# meped.net
KiCad netlist of a schematic drawn in EAGLE
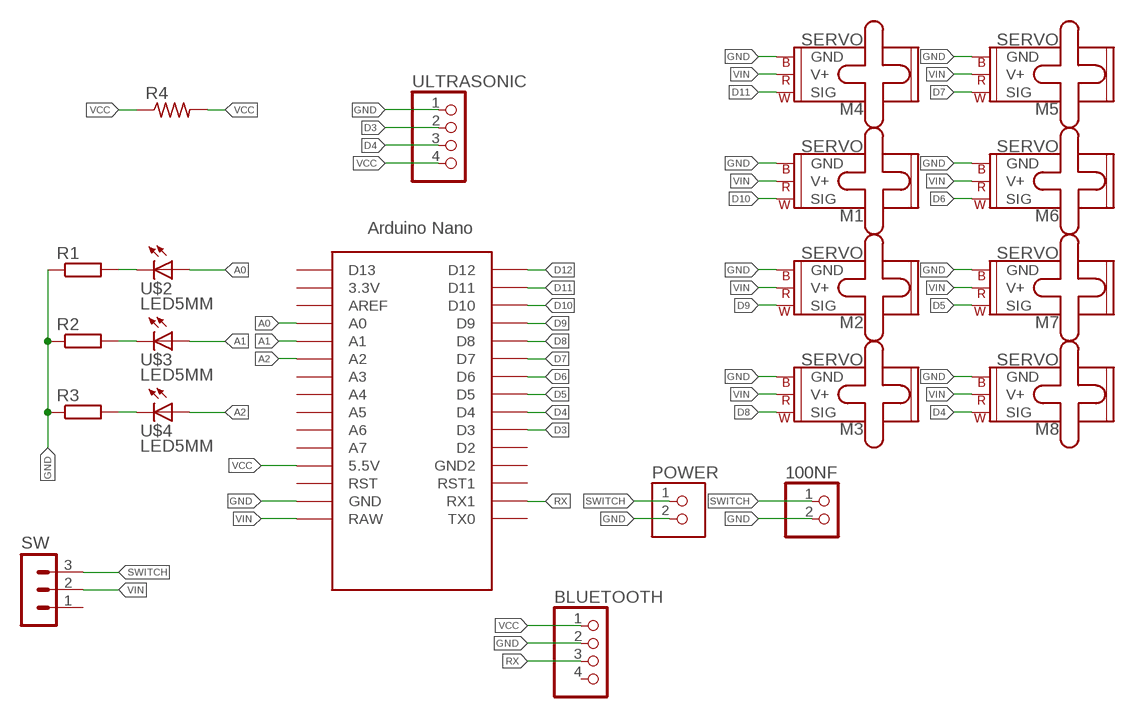
[diagram p0: schematic, sheet 1]

(export (version "E")
  (design (tool "Eeschema 10.0.6"))
  (components
    (comp (ref "100NF")
      (value "PINHD-1X2")
      (footprint "eagle-import:1X02")
      (libsource (lib "eagle-import") (part "PINHD-1X2"))
    )
    (comp (ref "BLUETOOTH")
      (value "PINHD-1X4")
      (footprint "eagle-import:1X04")
      (libsource (lib "eagle-import") (part "PINHD-1X4"))
    )
    (comp (ref "M1")
      (value "SERVO")
      (footprint "eagle-import:1X03")
      (libsource (lib "eagle-import") (part "SERVO"))
    )
    (comp (ref "M2")
      (value "SERVO")
      (footprint "eagle-import:1X03")
      (libsource (lib "eagle-import") (part "SERVO"))
    )
    (comp (ref "M3")
      (value "SERVO")
      (footprint "eagle-import:1X03")
      (libsource (lib "eagle-import") (part "SERVO"))
    )
    (comp (ref "M4")
      (value "SERVO")
      (footprint "eagle-import:1X03")
      (libsource (lib "eagle-import") (part "SERVO"))
    )
    (comp (ref "M5")
      (value "SERVO")
      (footprint "eagle-import:1X03")
      (libsource (lib "eagle-import") (part "SERVO"))
    )
    (comp (ref "M6")
      (value "SERVO")
      (footprint "eagle-import:1X03")
      (libsource (lib "eagle-import") (part "SERVO"))
    )
    (comp (ref "M7")
      (value "SERVO")
      (footprint "eagle-import:1X03")
      (libsource (lib "eagle-import") (part "SERVO"))
    )
    (comp (ref "M8")
      (value "SERVO")
      (footprint "eagle-import:1X03")
      (libsource (lib "eagle-import") (part "SERVO"))
    )
    (comp (ref "POWER")
      (value "TERM-1X02-ADAFRUIT")
      (footprint "eagle-import:3.5MMTERM")
      (libsource (lib "eagle-import") (part "TERM-1X02-ADAFRUIT"))
    )
    (comp (ref "R1")
      (value "R-EU_0204/5")
      (footprint "eagle-import:0204_5")
      (libsource (lib "eagle-import") (part "R-EU_0204/5"))
    )
    (comp (ref "R2")
      (value "R-EU_0204/5")
      (footprint "eagle-import:0204_5")
      (libsource (lib "eagle-import") (part "R-EU_0204/5"))
    )
    (comp (ref "R3")
      (value "R-EU_0204/5")
      (footprint "eagle-import:0204_5")
      (libsource (lib "eagle-import") (part "R-EU_0204/5"))
    )
    (comp (ref "R4")
      (value "RES-US1206FAB")
      (footprint "eagle-import:R1206FAB")
      (libsource (lib "eagle-import") (part "RES-US1206FAB"))
    )
    (comp (ref "SW")
      (value "MA03-1")
      (footprint "eagle-import:MA03-1")
      (libsource (lib "eagle-import") (part "MA03-1"))
    )
    (comp (ref "U$1")
      (value "NANO")
      (footprint "eagle-import:NANO")
      (libsource (lib "eagle-import") (part "NANO"))
    )
    (comp (ref "U$2")
      (value "LED5MM")
      (footprint "eagle-import:5MM")
      (libsource (lib "eagle-import") (part "LED5MM"))
    )
    (comp (ref "U$3")
      (value "LED5MM")
      (footprint "eagle-import:5MM")
      (libsource (lib "eagle-import") (part "LED5MM"))
    )
    (comp (ref "U$4")
      (value "LED5MM")
      (footprint "eagle-import:5MM")
      (libsource (lib "eagle-import") (part "LED5MM"))
    )
    (comp (ref "ULTRASONIC")
      (value "PINHD-1X4")
      (footprint "eagle-import:1X04")
      (libsource (lib "eagle-import") (part "PINHD-1X4"))
    )
  )
  (nets
    (net (code "1") (name "A0") (class "Default")
      (node (ref "U$1") (pin "A0") (pinfunction "A0_A0") (pintype "bidirectional"))
      (node (ref "U$2") (pin "IN") (pinfunction "A_IN") (pintype "passive"))
    )
    (net (code "2") (name "A1") (class "Default")
      (node (ref "U$1") (pin "A1") (pinfunction "A1_A1") (pintype "bidirectional"))
      (node (ref "U$3") (pin "IN") (pinfunction "A_IN") (pintype "passive"))
    )
    (net (code "3") (name "A2") (class "Default")
      (node (ref "U$1") (pin "A2") (pinfunction "A2_A2") (pintype "bidirectional"))
      (node (ref "U$4") (pin "IN") (pinfunction "A_IN") (pintype "passive"))
    )
    (net (code "4") (name "D3") (class "Default")
      (node (ref "U$1") (pin "D3") (pinfunction "D3_D3") (pintype "bidirectional"))
      (node (ref "ULTRASONIC") (pin "2") (pinfunction "2_2") (pintype "passive"))
    )
    (net (code "5") (name "D4") (class "Default")
      (node (ref "M8") (pin "1") (pinfunction "SIG_1") (pintype "bidirectional"))
      (node (ref "U$1") (pin "D4") (pinfunction "D4_D4") (pintype "bidirectional"))
      (node (ref "ULTRASONIC") (pin "3") (pinfunction "3_3") (pintype "passive"))
    )
    (net (code "6") (name "D5") (class "Default")
      (node (ref "M7") (pin "1") (pinfunction "SIG_1") (pintype "bidirectional"))
      (node (ref "U$1") (pin "D5") (pinfunction "D5_D5") (pintype "bidirectional"))
    )
    (net (code "7") (name "D6") (class "Default")
      (node (ref "M6") (pin "1") (pinfunction "SIG_1") (pintype "bidirectional"))
      (node (ref "U$1") (pin "D6") (pinfunction "D6_D6") (pintype "bidirectional"))
    )
    (net (code "8") (name "D7") (class "Default")
      (node (ref "M5") (pin "1") (pinfunction "SIG_1") (pintype "bidirectional"))
      (node (ref "U$1") (pin "D7") (pinfunction "D7_D7") (pintype "bidirectional"))
    )
    (net (code "9") (name "D8") (class "Default")
      (node (ref "M3") (pin "1") (pinfunction "SIG_1") (pintype "bidirectional"))
      (node (ref "U$1") (pin "D8") (pinfunction "D8_D8") (pintype "bidirectional"))
    )
    (net (code "10") (name "D9") (class "Default")
      (node (ref "M2") (pin "1") (pinfunction "SIG_1") (pintype "bidirectional"))
      (node (ref "U$1") (pin "D9") (pinfunction "D9_D9") (pintype "bidirectional"))
    )
    (net (code "11") (name "D10") (class "Default")
      (node (ref "M1") (pin "1") (pinfunction "SIG_1") (pintype "bidirectional"))
      (node (ref "U$1") (pin "D10") (pinfunction "D10_D10") (pintype "bidirectional"))
    )
    (net (code "12") (name "D11") (class "Default")
      (node (ref "M4") (pin "1") (pinfunction "SIG_1") (pintype "bidirectional"))
      (node (ref "U$1") (pin "D11") (pinfunction "D11_D11") (pintype "bidirectional"))
    )
    (net (code "13") (name "D12") (class "Default")
      (node (ref "U$1") (pin "D12") (pinfunction "D12_D12") (pintype "bidirectional"))
    )
    (net (code "14") (name "GND") (class "Default")
      (node (ref "100NF") (pin "2") (pinfunction "2_2") (pintype "passive"))
      (node (ref "BLUETOOTH") (pin "2") (pinfunction "2_2") (pintype "passive"))
      (node (ref "M1") (pin "3") (pinfunction "GND_3") (pintype "bidirectional"))
      (node (ref "M2") (pin "3") (pinfunction "GND_3") (pintype "bidirectional"))
      (node (ref "M3") (pin "3") (pinfunction "GND_3") (pintype "bidirectional"))
      (node (ref "M4") (pin "3") (pinfunction "GND_3") (pintype "bidirectional"))
      (node (ref "M5") (pin "3") (pinfunction "GND_3") (pintype "bidirectional"))
      (node (ref "M6") (pin "3") (pinfunction "GND_3") (pintype "bidirectional"))
      (node (ref "M7") (pin "3") (pinfunction "GND_3") (pintype "bidirectional"))
      (node (ref "M8") (pin "3") (pinfunction "GND_3") (pintype "bidirectional"))
      (node (ref "POWER") (pin "2") (pinfunction "2_2") (pintype "passive"))
      (node (ref "R1") (pin "1") (pinfunction "1_1") (pintype "passive"))
      (node (ref "R2") (pin "1") (pinfunction "1_1") (pintype "passive"))
      (node (ref "R3") (pin "1") (pinfunction "1_1") (pintype "passive"))
      (node (ref "U$1") (pin "GND") (pinfunction "GND_GND") (pintype "bidirectional"))
      (node (ref "ULTRASONIC") (pin "1") (pinfunction "1_1") (pintype "passive"))
    )
    (net (code "15") (name "Net-(U$2-C)") (class "Default")
      (node (ref "R1") (pin "2") (pinfunction "2_2") (pintype "passive"))
      (node (ref "U$2") (pin "OUT") (pinfunction "C_OUT") (pintype "passive"))
    )
    (net (code "16") (name "Net-(U$3-C)") (class "Default")
      (node (ref "R2") (pin "2") (pinfunction "2_2") (pintype "passive"))
      (node (ref "U$3") (pin "OUT") (pinfunction "C_OUT") (pintype "passive"))
    )
    (net (code "17") (name "Net-(U$4-C)") (class "Default")
      (node (ref "R3") (pin "2") (pinfunction "2_2") (pintype "passive"))
      (node (ref "U$4") (pin "OUT") (pinfunction "C_OUT") (pintype "passive"))
    )
    (net (code "18") (name "RX") (class "Default")
      (node (ref "BLUETOOTH") (pin "3") (pinfunction "3_3") (pintype "passive"))
      (node (ref "U$1") (pin "RX1") (pinfunction "RX1_RX1") (pintype "bidirectional"))
    )
    (net (code "19") (name "SWITCH") (class "Default")
      (node (ref "100NF") (pin "1") (pinfunction "1_1") (pintype "passive"))
      (node (ref "POWER") (pin "1") (pinfunction "1_1") (pintype "passive"))
      (node (ref "SW") (pin "3") (pinfunction "3_3") (pintype "passive"))
    )
    (net (code "20") (name "VCC") (class "Default")
      (node (ref "BLUETOOTH") (pin "1") (pinfunction "1_1") (pintype "passive"))
      (node (ref "R4") (pin "1") (pinfunction "1_1") (pintype "passive"))
      (node (ref "R4") (pin "2") (pinfunction "2_2") (pintype "passive"))
      (node (ref "U$1") (pin "5V") (pinfunction "5.5V_5V") (pintype "bidirectional"))
      (node (ref "ULTRASONIC") (pin "4") (pinfunction "4_4") (pintype "passive"))
    )
    (net (code "21") (name "VIN") (class "Default")
      (node (ref "M1") (pin "2") (pinfunction "V+_2") (pintype "bidirectional"))
      (node (ref "M2") (pin "2") (pinfunction "V+_2") (pintype "bidirectional"))
      (node (ref "M3") (pin "2") (pinfunction "V+_2") (pintype "bidirectional"))
      (node (ref "M4") (pin "2") (pinfunction "V+_2") (pintype "bidirectional"))
      (node (ref "M5") (pin "2") (pinfunction "V+_2") (pintype "bidirectional"))
      (node (ref "M6") (pin "2") (pinfunction "V+_2") (pintype "bidirectional"))
      (node (ref "M7") (pin "2") (pinfunction "V+_2") (pintype "bidirectional"))
      (node (ref "M8") (pin "2") (pinfunction "V+_2") (pintype "bidirectional"))
      (node (ref "SW") (pin "2") (pinfunction "2_2") (pintype "passive"))
      (node (ref "U$1") (pin "RAW") (pinfunction "RAW_RAW") (pintype "bidirectional"))
    )
    (net (code "22") (name "unconnected-(BLUETOOTH-Pad4)") (class "Default")
      (node (ref "BLUETOOTH") (pin "4") (pinfunction "4_4") (pintype "passive"))
    )
    (net (code "23") (name "unconnected-(SW-Pad1)") (class "Default")
      (node (ref "SW") (pin "1") (pinfunction "1_1") (pintype "passive"))
    )
    (net (code "24") (name "unconnected-(U$1-GND2-PadGND1)") (class "Default")
      (node (ref "U$1") (pin "GND1") (pinfunction "GND2_GND1") (pintype "bidirectional"))
    )
    (net (code "25") (name "unconnected-(U$1-Pad3.3V)") (class "Default")
      (node (ref "U$1") (pin "3.3V") (pinfunction "3.3V_3.3V") (pintype "bidirectional"))
    )
    (net (code "26") (name "unconnected-(U$1-PadA3)") (class "Default")
      (node (ref "U$1") (pin "A3") (pinfunction "A3_A3") (pintype "bidirectional"))
    )
    (net (code "27") (name "unconnected-(U$1-PadA4)") (class "Default")
      (node (ref "U$1") (pin "A4") (pinfunction "A4_A4") (pintype "bidirectional"))
    )
    (net (code "28") (name "unconnected-(U$1-PadA5)") (class "Default")
      (node (ref "U$1") (pin "A5") (pinfunction "A5_A5") (pintype "bidirectional"))
    )
    (net (code "29") (name "unconnected-(U$1-PadA6)") (class "Default")
      (node (ref "U$1") (pin "A6") (pinfunction "A6_A6") (pintype "bidirectional"))
    )
    (net (code "30") (name "unconnected-(U$1-PadA7)") (class "Default")
      (node (ref "U$1") (pin "A7") (pinfunction "A7_A7") (pintype "bidirectional"))
    )
    (net (code "31") (name "unconnected-(U$1-PadAREF)") (class "Default")
      (node (ref "U$1") (pin "AREF") (pinfunction "AREF_AREF") (pintype "bidirectional"))
    )
    (net (code "32") (name "unconnected-(U$1-PadD2)") (class "Default")
      (node (ref "U$1") (pin "D2") (pinfunction "D2_D2") (pintype "bidirectional"))
    )
    (net (code "33") (name "unconnected-(U$1-PadD13)") (class "Default")
      (node (ref "U$1") (pin "D13") (pinfunction "D13_D13") (pintype "bidirectional"))
    )
    (net (code "34") (name "unconnected-(U$1-PadICSP1)") (class "Default")
      (node (ref "U$1") (pin "ICSP1") (pinfunction "ICSP1_ICSP1") (pintype "bidirectional"))
    )
    (net (code "35") (name "unconnected-(U$1-PadICSP2)") (class "Default")
      (node (ref "U$1") (pin "ICSP2") (pinfunction "ICSP2_ICSP2") (pintype "bidirectional"))
    )
    (net (code "36") (name "unconnected-(U$1-PadICSP3)") (class "Default")
      (node (ref "U$1") (pin "ICSP3") (pinfunction "ICSP3_ICSP3") (pintype "bidirectional"))
    )
    (net (code "37") (name "unconnected-(U$1-PadICSP4)") (class "Default")
      (node (ref "U$1") (pin "ICSP4") (pinfunction "ICSP4_ICSP4") (pintype "bidirectional"))
    )
    (net (code "38") (name "unconnected-(U$1-PadICSP5)") (class "Default")
      (node (ref "U$1") (pin "ICSP5") (pinfunction "ICSP5_ICSP5") (pintype "bidirectional"))
    )
    (net (code "39") (name "unconnected-(U$1-PadICSP6)") (class "Default")
      (node (ref "U$1") (pin "ICSP6") (pinfunction "ICSP6_ICSP6") (pintype "bidirectional"))
    )
    (net (code "40") (name "unconnected-(U$1-PadRST)") (class "Default")
      (node (ref "U$1") (pin "RST") (pinfunction "RST_RST") (pintype "bidirectional"))
    )
    (net (code "41") (name "unconnected-(U$1-PadRST1)") (class "Default")
      (node (ref "U$1") (pin "RST1") (pinfunction "RST1_RST1") (pintype "bidirectional"))
    )
    (net (code "42") (name "unconnected-(U$1-PadTX0)") (class "Default")
      (node (ref "U$1") (pin "TX0") (pinfunction "TX0_TX0") (pintype "bidirectional"))
    )
  )
)
